# PortaCopos.net
KiCad netlist of a schematic drawn in EAGLE
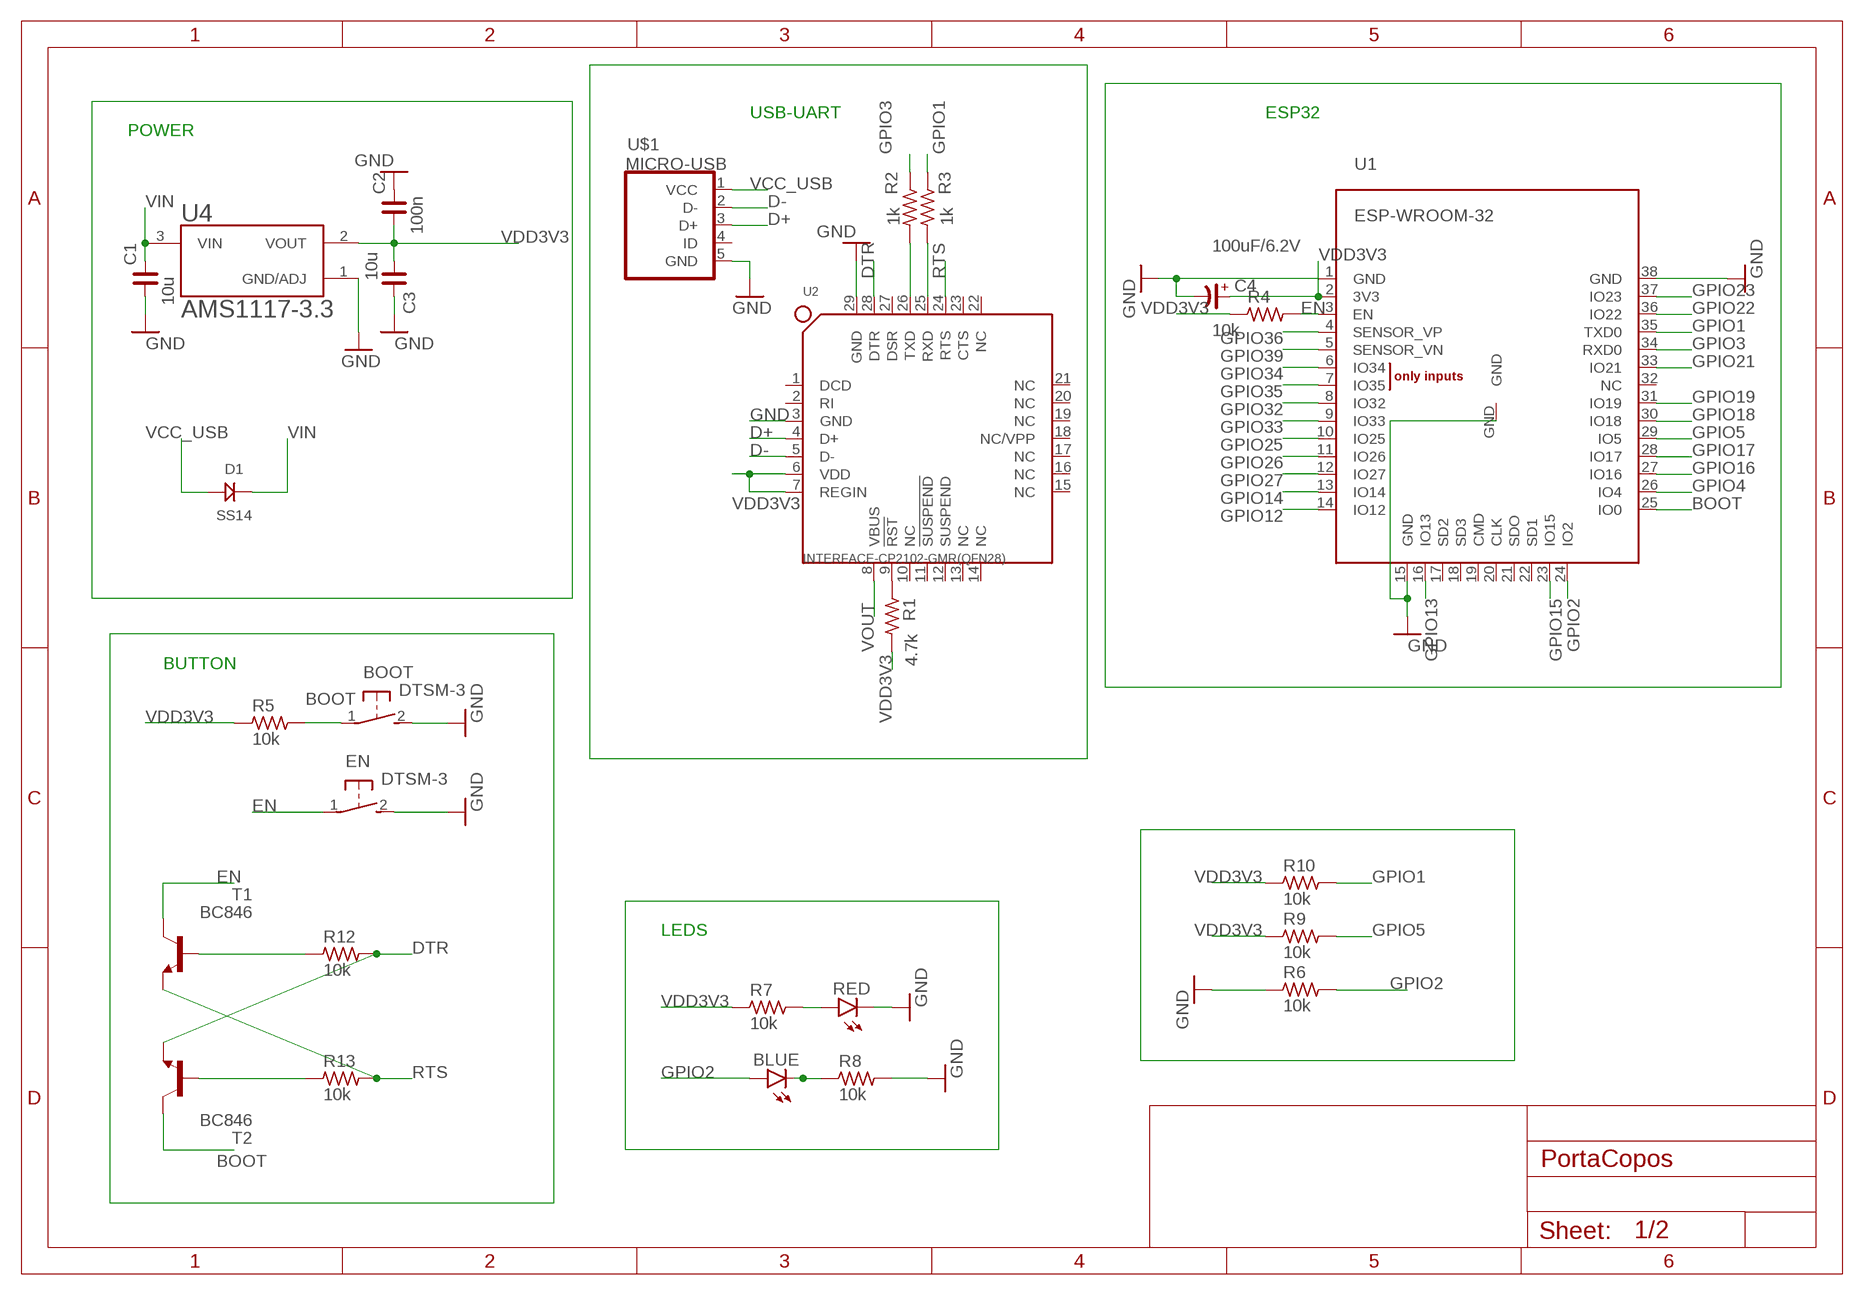
[diagram p0: schematic, sheet 1]
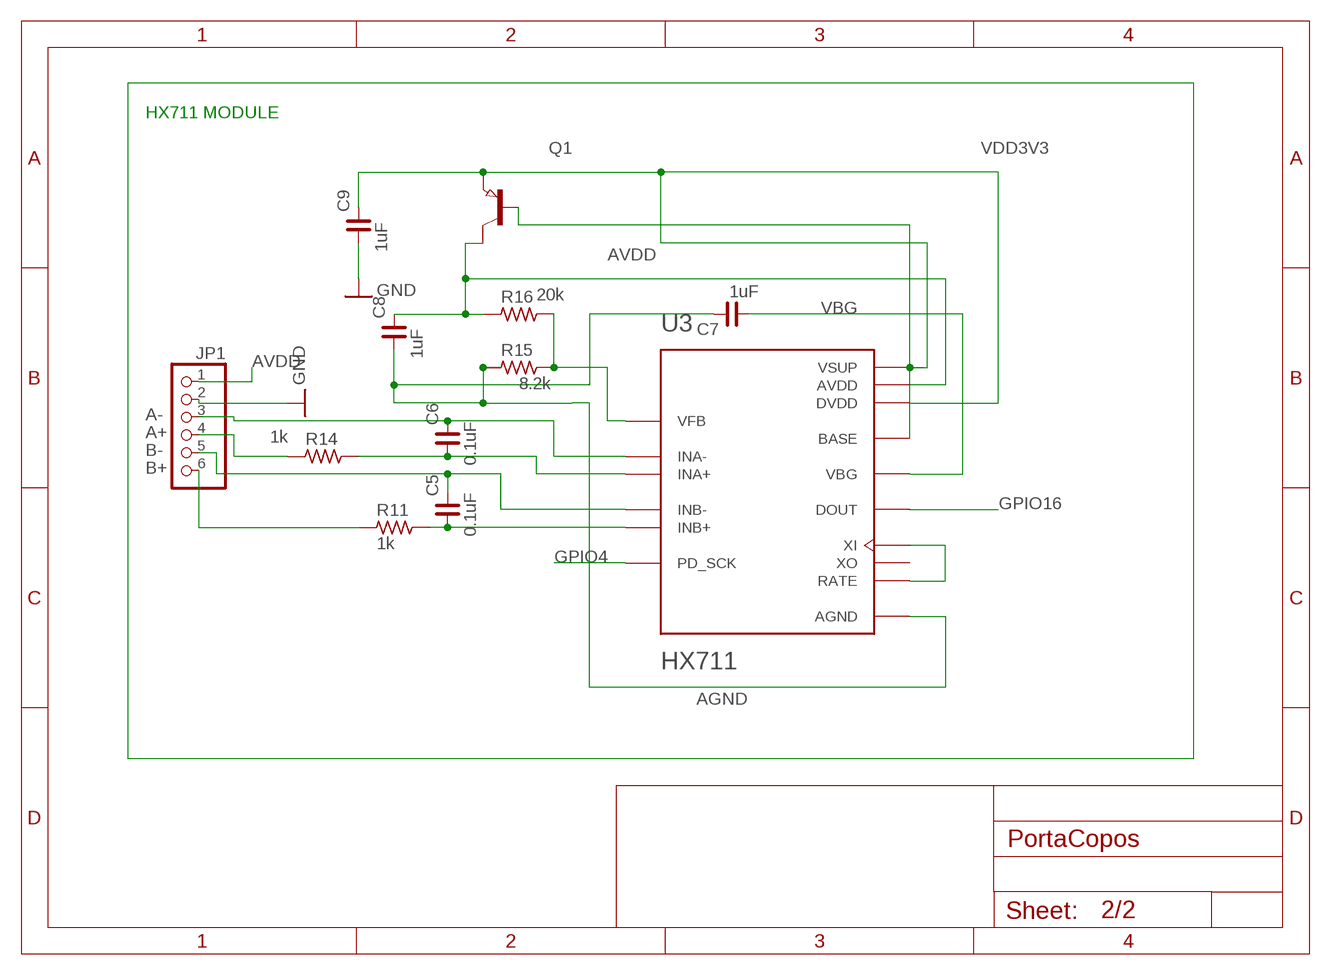
[diagram p1: schematic, sheet 2]

(export (version "E")
  (design (tool "Eeschema 10.0.6"))
  (components
    (comp (ref "BLUE")
      (value "blue")
      (footprint "eagle-import:CHIPLED_0603")
      (libsource (lib "eagle-import") (part "LEDCHIPLED_0603"))
    )
    (comp (ref "BOOT")
      (value "DTSM-3")
      (footprint "eagle-import:DTSM-3")
      (libsource (lib "eagle-import") (part "DTSM-3"))
    )
    (comp (ref "C1")
      (value "10u")
      (footprint "eagle-import:C0603")
      (libsource (lib "eagle-import") (part "C_0603"))
    )
    (comp (ref "C2")
      (value "100n")
      (footprint "eagle-import:C0603")
      (libsource (lib "eagle-import") (part "C_0603"))
    )
    (comp (ref "C3")
      (value "10u")
      (footprint "eagle-import:C0603")
      (libsource (lib "eagle-import") (part "C_0603"))
    )
    (comp (ref "C4")
      (value "100uF/6.2V")
      (footprint "eagle-import:C3216-18_T")
      (libsource (lib "eagle-import") (part "CP_3216-18"))
    )
    (comp (ref "D1")
      (value "SS14")
      (footprint "eagle-import:DO214")
      (fields (field (name "MF") "ON Semiconductor"))
      (libsource (lib "eagle-import") (part "SS14"))
    )
    (comp (ref "EN")
      (value "DTSM-3")
      (footprint "eagle-import:DTSM-3")
      (libsource (lib "eagle-import") (part "DTSM-3"))
    )
    (comp (ref "R1")
      (value "4.7k")
      (footprint "eagle-import:R0603")
      (libsource (lib "eagle-import") (part "R_0603"))
    )
    (comp (ref "R2")
      (value "1k")
      (footprint "eagle-import:R0603")
      (libsource (lib "eagle-import") (part "R_0603"))
    )
    (comp (ref "R3")
      (value "1k")
      (footprint "eagle-import:R0603")
      (libsource (lib "eagle-import") (part "R_0603"))
    )
    (comp (ref "R4")
      (value "10k")
      (footprint "eagle-import:R0603")
      (libsource (lib "eagle-import") (part "R_0603"))
    )
    (comp (ref "R5")
      (value "10k")
      (footprint "eagle-import:R0603")
      (libsource (lib "eagle-import") (part "R_0603"))
    )
    (comp (ref "R6")
      (value "10k")
      (footprint "eagle-import:R0603")
      (libsource (lib "eagle-import") (part "R_0603"))
    )
    (comp (ref "R7")
      (value "10k")
      (footprint "eagle-import:R0603")
      (libsource (lib "eagle-import") (part "R_0603"))
    )
    (comp (ref "R8")
      (value "10k")
      (footprint "eagle-import:R0603")
      (libsource (lib "eagle-import") (part "R_0603"))
    )
    (comp (ref "R9")
      (value "10k")
      (footprint "eagle-import:R0603")
      (libsource (lib "eagle-import") (part "R_0603"))
    )
    (comp (ref "R10")
      (value "10k")
      (footprint "eagle-import:R0603")
      (libsource (lib "eagle-import") (part "R_0603"))
    )
    (comp (ref "R12")
      (value "10k")
      (footprint "eagle-import:R0603")
      (libsource (lib "eagle-import") (part "R_0603"))
    )
    (comp (ref "R13")
      (value "10k")
      (footprint "eagle-import:R0603")
      (libsource (lib "eagle-import") (part "R_0603"))
    )
    (comp (ref "RED")
      (value "red")
      (footprint "eagle-import:CHIPLED_0603")
      (libsource (lib "eagle-import") (part "LEDCHIPLED_0603"))
    )
    (comp (ref "T1")
      (value "BC846")
      (footprint "eagle-import:SOT23")
      (libsource (lib "eagle-import") (part "BC846"))
    )
    (comp (ref "T2")
      (value "BC846")
      (footprint "eagle-import:SOT23")
      (libsource (lib "eagle-import") (part "BC846"))
    )
    (comp (ref "U$1")
      (value "MICRO-USB")
      (footprint "eagle-import:MICRO-USB-2")
      (libsource (lib "eagle-import") (part "MICRO-USB"))
    )
    (comp (ref "U1")
      (value "ESP-WROOM-32")
      (footprint "eagle-import:ESP-WROOM-32")
      (libsource (lib "eagle-import") (part "ESP-WROOM-32"))
    )
    (comp (ref "U2")
      (value "INTERFACE-CP2102-GMR(QFN28)")
      (footprint "eagle-import:QFN28G_0.5-5X5MM")
      (fields (field (name "MF") "Silicon") (field (name "MP") "CP2102-GMR"))
      (libsource (lib "eagle-import") (part "INTERFACE-CP2102-GMR(QFN28)"))
    )
    (comp (ref "U4")
      (value "AMS1117-3.3")
      (footprint "eagle-import:SOT229P700X180-4N")
      (fields (field (name "MF") "Advanced Monolithic Systems"))
      (libsource (lib "eagle-import") (part "AMS1117-3.3"))
    )
    (comp (ref "C5")
      (value "0.1uF")
      (footprint "eagle-import:C0805")
      (libsource (lib "eagle-import") (part "C_0805"))
    )
    (comp (ref "C6")
      (value "0.1uF")
      (footprint "eagle-import:C0805")
      (libsource (lib "eagle-import") (part "C_0805"))
    )
    (comp (ref "C7")
      (value "1uF")
      (footprint "eagle-import:C0805")
      (libsource (lib "eagle-import") (part "C_0805"))
    )
    (comp (ref "C8")
      (value "1uF")
      (footprint "eagle-import:C0805")
      (libsource (lib "eagle-import") (part "C_0805"))
    )
    (comp (ref "C9")
      (value "1uF")
      (footprint "eagle-import:C0805")
      (libsource (lib "eagle-import") (part "C_0805"))
    )
    (comp (ref "JP1")
      (value "PINHD-1X6")
      (footprint "eagle-import:1X06")
      (libsource (lib "eagle-import") (part "PINHD-1X6"))
    )
    (comp (ref "Q1")
      (value "PNP-TRANSISTOR_SOT23")
      (footprint "eagle-import:SOT23")
      (libsource (lib "eagle-import") (part "PNP-TRANSISTOR_SOT23"))
    )
    (comp (ref "R11")
      (value "1k")
      (footprint "eagle-import:R0603")
      (libsource (lib "eagle-import") (part "R_0603"))
    )
    (comp (ref "R14")
      (value "1k")
      (footprint "eagle-import:R0603")
      (libsource (lib "eagle-import") (part "R_0603"))
    )
    (comp (ref "R15")
      (value "8.2k")
      (footprint "eagle-import:R0603")
      (libsource (lib "eagle-import") (part "R_0603"))
    )
    (comp (ref "R16")
      (value "20k")
      (footprint "eagle-import:R0603")
      (libsource (lib "eagle-import") (part "R_0603"))
    )
    (comp (ref "U3")
      (value "HX711")
      (footprint "eagle-import:SOP127P600X180-16N")
      (fields (field (name "MF") "AVIA SEMICONDUCTOR"))
      (libsource (lib "eagle-import") (part "HX711"))
    )
  )
  (nets
    (net (code "1") (name "A+") (class "Default")
      (node (ref "JP1") (pin "4") (pinfunction "4_4") (pintype "passive"))
      (node (ref "R14") (pin "1") (pinfunction "1_1") (pintype "passive"))
    )
    (net (code "2") (name "A-") (class "Default")
      (node (ref "C6") (pin "2") (pinfunction "2_2") (pintype "passive"))
      (node (ref "JP1") (pin "3") (pinfunction "3_3") (pintype "passive"))
      (node (ref "U3") (pin "7") (pinfunction "INA-_7") (pintype "input"))
    )
    (net (code "3") (name "AGND") (class "Default")
      (node (ref "C7") (pin "2") (pinfunction "2_2") (pintype "passive"))
      (node (ref "C8") (pin "1") (pinfunction "1_1") (pintype "passive"))
      (node (ref "R15") (pin "1") (pinfunction "1_1") (pintype "passive"))
      (node (ref "U3") (pin "5") (pinfunction "AGND_5") (pintype "power_in"))
    )
    (net (code "4") (name "AVDD") (class "Default")
      (node (ref "C8") (pin "2") (pinfunction "2_2") (pintype "passive"))
      (node (ref "JP1") (pin "1") (pinfunction "1_1") (pintype "passive"))
      (node (ref "Q1") (pin "3") (pinfunction "C_3") (pintype "passive"))
      (node (ref "R16") (pin "1") (pinfunction "1_1") (pintype "passive"))
      (node (ref "U3") (pin "3") (pinfunction "AVDD_3") (pintype "power_in"))
    )
    (net (code "5") (name "B+") (class "Default")
      (node (ref "JP1") (pin "6") (pinfunction "6_6") (pintype "passive"))
      (node (ref "R11") (pin "1") (pinfunction "1_1") (pintype "passive"))
    )
    (net (code "6") (name "B-") (class "Default")
      (node (ref "C5") (pin "2") (pinfunction "2_2") (pintype "passive"))
      (node (ref "JP1") (pin "5") (pinfunction "5_5") (pintype "passive"))
      (node (ref "U3") (pin "9") (pinfunction "INB-_9") (pintype "input"))
    )
    (net (code "7") (name "BOOT") (class "Default")
      (node (ref "BOOT") (pin "1") (pinfunction "1_1") (pintype "passive"))
      (node (ref "R5") (pin "2") (pinfunction "2_2") (pintype "passive"))
      (node (ref "T2") (pin "3") (pinfunction "C_3") (pintype "passive"))
      (node (ref "U1") (pin "25") (pinfunction "IO0_25") (pintype "bidirectional"))
    )
    (net (code "8") (name "D+") (class "Default")
      (node (ref "U$1") (pin "3") (pinfunction "D+_3") (pintype "bidirectional"))
      (node (ref "U2") (pin "4") (pinfunction "D+_4") (pintype "bidirectional"))
    )
    (net (code "9") (name "D-") (class "Default")
      (node (ref "U$1") (pin "2") (pinfunction "D-_2") (pintype "bidirectional"))
      (node (ref "U2") (pin "5") (pinfunction "D-_5") (pintype "bidirectional"))
    )
    (net (code "10") (name "DTR") (class "Default")
      (node (ref "R12") (pin "2") (pinfunction "2_2") (pintype "passive"))
      (node (ref "T2") (pin "2") (pinfunction "E_2") (pintype "passive"))
      (node (ref "U2") (pin "28") (pinfunction "DTR_28") (pintype "bidirectional"))
    )
    (net (code "11") (name "EN") (class "Default")
      (node (ref "EN") (pin "1") (pinfunction "1_1") (pintype "passive"))
      (node (ref "R4") (pin "2") (pinfunction "2_2") (pintype "passive"))
      (node (ref "T1") (pin "3") (pinfunction "C_3") (pintype "passive"))
      (node (ref "U1") (pin "3") (pinfunction "EN_3") (pintype "bidirectional"))
    )
    (net (code "12") (name "GND") (class "Default")
      (node (ref "BOOT") (pin "2") (pinfunction "2_2") (pintype "passive"))
      (node (ref "C1") (pin "1") (pinfunction "1_1") (pintype "passive"))
      (node (ref "C2") (pin "2") (pinfunction "2_2") (pintype "passive"))
      (node (ref "C3") (pin "2") (pinfunction "2_2") (pintype "passive"))
      (node (ref "C4") (pin "-") (pinfunction "-_-") (pintype "passive"))
      (node (ref "C9") (pin "1") (pinfunction "1_1") (pintype "passive"))
      (node (ref "EN") (pin "2") (pinfunction "2_2") (pintype "passive"))
      (node (ref "JP1") (pin "2") (pinfunction "2_2") (pintype "passive"))
      (node (ref "R6") (pin "1") (pinfunction "1_1") (pintype "passive"))
      (node (ref "R8") (pin "2") (pinfunction "2_2") (pintype "passive"))
      (node (ref "RED") (pin "C") (pinfunction "C_C") (pintype "passive"))
      (node (ref "U$1") (pin "5") (pinfunction "GND_5") (pintype "power_in"))
      (node (ref "U1") (pin "1") (pinfunction "GND_1") (pintype "bidirectional"))
      (node (ref "U1") (pin "15") (pinfunction "GND_15") (pintype "bidirectional"))
      (node (ref "U1") (pin "38") (pinfunction "GND_38") (pintype "bidirectional"))
      (node (ref "U1") (pin "GND") (pinfunction "GND_GND") (pintype "bidirectional"))
      (node (ref "U2") (pin "29") (pinfunction "GND_29") (pintype "bidirectional"))
      (node (ref "U2") (pin "3") (pinfunction "GND_3") (pintype "bidirectional"))
      (node (ref "U4") (pin "1") (pinfunction "GND/ADJ_1") (pintype "power_in"))
    )
    (net (code "13") (name "GPIO1") (class "Default")
      (node (ref "R10") (pin "2") (pinfunction "2_2") (pintype "passive"))
      (node (ref "R3") (pin "1") (pinfunction "1_1") (pintype "passive"))
      (node (ref "U1") (pin "35") (pinfunction "TXD0_35") (pintype "bidirectional"))
    )
    (net (code "14") (name "GPIO2") (class "Default")
      (node (ref "BLUE") (pin "A") (pinfunction "A_A") (pintype "passive"))
      (node (ref "R6") (pin "2") (pinfunction "2_2") (pintype "passive"))
      (node (ref "U1") (pin "24") (pinfunction "IO2_24") (pintype "bidirectional"))
    )
    (net (code "15") (name "GPIO3") (class "Default")
      (node (ref "R2") (pin "1") (pinfunction "1_1") (pintype "passive"))
      (node (ref "U1") (pin "34") (pinfunction "RXD0_34") (pintype "bidirectional"))
    )
    (net (code "16") (name "GPIO4") (class "Default")
      (node (ref "U1") (pin "26") (pinfunction "IO4_26") (pintype "bidirectional"))
      (node (ref "U3") (pin "11") (pinfunction "PD_SCK_11") (pintype "input"))
    )
    (net (code "17") (name "GPIO5") (class "Default")
      (node (ref "R9") (pin "2") (pinfunction "2_2") (pintype "passive"))
      (node (ref "U1") (pin "29") (pinfunction "IO5_29") (pintype "bidirectional"))
    )
    (net (code "18") (name "GPIO12") (class "Default")
      (node (ref "U1") (pin "14") (pinfunction "IO12_14") (pintype "bidirectional"))
    )
    (net (code "19") (name "GPIO13") (class "Default")
      (node (ref "U1") (pin "16") (pinfunction "IO13_16") (pintype "bidirectional"))
    )
    (net (code "20") (name "GPIO14") (class "Default")
      (node (ref "U1") (pin "13") (pinfunction "IO14_13") (pintype "bidirectional"))
    )
    (net (code "21") (name "GPIO15") (class "Default")
      (node (ref "U1") (pin "23") (pinfunction "IO15_23") (pintype "bidirectional"))
    )
    (net (code "22") (name "GPIO16") (class "Default")
      (node (ref "U1") (pin "27") (pinfunction "IO16_27") (pintype "bidirectional"))
      (node (ref "U3") (pin "12") (pinfunction "DOUT_12") (pintype "output"))
    )
    (net (code "23") (name "GPIO17") (class "Default")
      (node (ref "U1") (pin "28") (pinfunction "IO17_28") (pintype "bidirectional"))
    )
    (net (code "24") (name "GPIO18") (class "Default")
      (node (ref "U1") (pin "30") (pinfunction "IO18_30") (pintype "bidirectional"))
    )
    (net (code "25") (name "GPIO19") (class "Default")
      (node (ref "U1") (pin "31") (pinfunction "IO19_31") (pintype "bidirectional"))
    )
    (net (code "26") (name "GPIO21") (class "Default")
      (node (ref "U1") (pin "33") (pinfunction "IO21_33") (pintype "bidirectional"))
    )
    (net (code "27") (name "GPIO22") (class "Default")
      (node (ref "U1") (pin "36") (pinfunction "IO22_36") (pintype "bidirectional"))
    )
    (net (code "28") (name "GPIO23") (class "Default")
      (node (ref "U1") (pin "37") (pinfunction "IO23_37") (pintype "bidirectional"))
    )
    (net (code "29") (name "GPIO25") (class "Default")
      (node (ref "U1") (pin "10") (pinfunction "IO25_10") (pintype "bidirectional"))
    )
    (net (code "30") (name "GPIO26") (class "Default")
      (node (ref "U1") (pin "11") (pinfunction "IO26_11") (pintype "bidirectional"))
    )
    (net (code "31") (name "GPIO27") (class "Default")
      (node (ref "U1") (pin "12") (pinfunction "IO27_12") (pintype "bidirectional"))
    )
    (net (code "32") (name "GPIO32") (class "Default")
      (node (ref "U1") (pin "8") (pinfunction "IO32_8") (pintype "bidirectional"))
    )
    (net (code "33") (name "GPIO33") (class "Default")
      (node (ref "U1") (pin "9") (pinfunction "IO33_9") (pintype "bidirectional"))
    )
    (net (code "34") (name "GPIO34") (class "Default")
      (node (ref "U1") (pin "6") (pinfunction "IO34_6") (pintype "input"))
    )
    (net (code "35") (name "GPIO35") (class "Default")
      (node (ref "U1") (pin "7") (pinfunction "IO35_7") (pintype "input"))
    )
    (net (code "36") (name "GPIO36") (class "Default")
      (node (ref "U1") (pin "4") (pinfunction "SENSOR_VP_4") (pintype "input"))
    )
    (net (code "37") (name "GPIO39") (class "Default")
      (node (ref "U1") (pin "5") (pinfunction "SENSOR_VN_5") (pintype "input"))
    )
    (net (code "38") (name "Net-(BLUE-PadC)") (class "Default")
      (node (ref "BLUE") (pin "C") (pinfunction "C_C") (pintype "passive"))
      (node (ref "R8") (pin "1") (pinfunction "1_1") (pintype "passive"))
    )
    (net (code "39") (name "Net-(R7-Pad2)") (class "Default")
      (node (ref "R7") (pin "2") (pinfunction "2_2") (pintype "passive"))
      (node (ref "RED") (pin "A") (pinfunction "A_A") (pintype "passive"))
    )
    (net (code "40") (name "Net-(T1-B)") (class "Default")
      (node (ref "R12") (pin "1") (pinfunction "1_1") (pintype "passive"))
      (node (ref "T1") (pin "1") (pinfunction "B_1") (pintype "passive"))
    )
    (net (code "41") (name "Net-(T2-B)") (class "Default")
      (node (ref "R13") (pin "1") (pinfunction "1_1") (pintype "passive"))
      (node (ref "T2") (pin "1") (pinfunction "B_1") (pintype "passive"))
    )
    (net (code "42") (name "Net-(U2-RXD)") (class "Default")
      (node (ref "R3") (pin "2") (pinfunction "2_2") (pintype "passive"))
      (node (ref "U2") (pin "25") (pinfunction "RXD_25") (pintype "bidirectional"))
    )
    (net (code "43") (name "Net-(U2-TXD)") (class "Default")
      (node (ref "R2") (pin "2") (pinfunction "2_2") (pintype "passive"))
      (node (ref "U2") (pin "26") (pinfunction "TXD_26") (pintype "bidirectional"))
    )
    (net (code "44") (name "Net-(U2-~{RST})") (class "Default")
      (node (ref "R1") (pin "1") (pinfunction "1_1") (pintype "passive"))
      (node (ref "U2") (pin "9") (pinfunction "~{RST}_9") (pintype "bidirectional"))
    )
    (net (code "45") (name "Net-(U3-INA+)") (class "Default")
      (node (ref "C6") (pin "1") (pinfunction "1_1") (pintype "passive"))
      (node (ref "R14") (pin "2") (pinfunction "2_2") (pintype "passive"))
      (node (ref "U3") (pin "8") (pinfunction "INA+_8") (pintype "input"))
    )
    (net (code "46") (name "Net-(U3-INB+)") (class "Default")
      (node (ref "C5") (pin "1") (pinfunction "1_1") (pintype "passive"))
      (node (ref "R11") (pin "2") (pinfunction "2_2") (pintype "passive"))
      (node (ref "U3") (pin "10") (pinfunction "INB+_10") (pintype "input"))
    )
    (net (code "47") (name "Net-(U3-RATE)") (class "Default")
      (node (ref "U3") (pin "14") (pinfunction "XI_14") (pintype "input"))
      (node (ref "U3") (pin "15") (pinfunction "RATE_15") (pintype "input"))
    )
    (net (code "48") (name "Net-(U3-VFB)") (class "Default")
      (node (ref "R15") (pin "2") (pinfunction "2_2") (pintype "passive"))
      (node (ref "R16") (pin "2") (pinfunction "2_2") (pintype "passive"))
      (node (ref "U3") (pin "4") (pinfunction "VFB_4") (pintype "input"))
    )
    (net (code "49") (name "RTS") (class "Default")
      (node (ref "R13") (pin "2") (pinfunction "2_2") (pintype "passive"))
      (node (ref "T1") (pin "2") (pinfunction "E_2") (pintype "passive"))
      (node (ref "U2") (pin "24") (pinfunction "RTS_24") (pintype "bidirectional"))
    )
    (net (code "50") (name "VBG") (class "Default")
      (node (ref "C7") (pin "1") (pinfunction "1_1") (pintype "passive"))
      (node (ref "U3") (pin "6") (pinfunction "VBG_6") (pintype "output"))
    )
    (net (code "51") (name "VCC_USB") (class "Default")
      (node (ref "D1") (pin "ANODE") (pinfunction "ANODE_ANODE") (pintype "bidirectional"))
      (node (ref "U$1") (pin "1") (pinfunction "VCC_1") (pintype "power_in"))
    )
    (net (code "52") (name "VDD3V3") (class "Default")
      (node (ref "C2") (pin "1") (pinfunction "1_1") (pintype "passive"))
      (node (ref "C3") (pin "1") (pinfunction "1_1") (pintype "passive"))
      (node (ref "C4") (pin "+") (pinfunction "+_+") (pintype "passive"))
      (node (ref "C9") (pin "2") (pinfunction "2_2") (pintype "passive"))
      (node (ref "Q1") (pin "1") (pinfunction "B_1") (pintype "passive"))
      (node (ref "Q1") (pin "2") (pinfunction "E_2") (pintype "passive"))
      (node (ref "R1") (pin "2") (pinfunction "2_2") (pintype "passive"))
      (node (ref "R10") (pin "1") (pinfunction "1_1") (pintype "passive"))
      (node (ref "R4") (pin "1") (pinfunction "1_1") (pintype "passive"))
      (node (ref "R5") (pin "1") (pinfunction "1_1") (pintype "passive"))
      (node (ref "R7") (pin "1") (pinfunction "1_1") (pintype "passive"))
      (node (ref "R9") (pin "1") (pinfunction "1_1") (pintype "passive"))
      (node (ref "U1") (pin "2") (pinfunction "3V3_2") (pintype "bidirectional"))
      (node (ref "U2") (pin "6") (pinfunction "VDD_6") (pintype "bidirectional"))
      (node (ref "U2") (pin "7") (pinfunction "REGIN_7") (pintype "bidirectional"))
      (node (ref "U3") (pin "1") (pinfunction "VSUP_1") (pintype "power_in"))
      (node (ref "U3") (pin "16") (pinfunction "DVDD_16") (pintype "power_in"))
      (node (ref "U3") (pin "2") (pinfunction "BASE_2") (pintype "output"))
      (node (ref "U4") (pin "2") (pinfunction "VOUT_2") (pintype "output"))
    )
    (net (code "53") (name "VIN") (class "Default")
      (node (ref "C1") (pin "2") (pinfunction "2_2") (pintype "passive"))
      (node (ref "D1") (pin "CATHODE") (pinfunction "KATHODE_CATHODE") (pintype "bidirectional"))
      (node (ref "U4") (pin "3") (pinfunction "VIN_3") (pintype "input"))
    )
    (net (code "54") (name "VOUT") (class "Default")
      (node (ref "U2") (pin "8") (pinfunction "VBUS_8") (pintype "bidirectional"))
    )
    (net (code "55") (name "unconnected-(U$1-ID-Pad4)") (class "Default")
      (node (ref "U$1") (pin "4") (pinfunction "ID_4") (pintype "bidirectional"))
    )
    (net (code "56") (name "unconnected-(U1-CLK-Pad20)") (class "Default")
      (node (ref "U1") (pin "20") (pinfunction "CLK_20") (pintype "bidirectional"))
    )
    (net (code "57") (name "unconnected-(U1-CMD-Pad19)") (class "Default")
      (node (ref "U1") (pin "19") (pinfunction "CMD_19") (pintype "bidirectional"))
    )
    (net (code "58") (name "unconnected-(U1-NC-Pad32)") (class "Default")
      (node (ref "U1") (pin "32") (pinfunction "NC_32") (pintype "bidirectional"))
    )
    (net (code "59") (name "unconnected-(U1-SD1-Pad22)") (class "Default")
      (node (ref "U1") (pin "22") (pinfunction "SD1_22") (pintype "bidirectional"))
    )
    (net (code "60") (name "unconnected-(U1-SD2-Pad17)") (class "Default")
      (node (ref "U1") (pin "17") (pinfunction "SD2_17") (pintype "bidirectional"))
    )
    (net (code "61") (name "unconnected-(U1-SD3-Pad18)") (class "Default")
      (node (ref "U1") (pin "18") (pinfunction "SD3_18") (pintype "bidirectional"))
    )
    (net (code "62") (name "unconnected-(U1-SDO-Pad21)") (class "Default")
      (node (ref "U1") (pin "21") (pinfunction "SDO_21") (pintype "bidirectional"))
    )
    (net (code "63") (name "unconnected-(U2-CTS-Pad23)") (class "Default")
      (node (ref "U2") (pin "23") (pinfunction "CTS_23") (pintype "bidirectional"))
    )
    (net (code "64") (name "unconnected-(U2-DCD-Pad1)") (class "Default")
      (node (ref "U2") (pin "1") (pinfunction "DCD_1") (pintype "bidirectional"))
    )
    (net (code "65") (name "unconnected-(U2-DSR-Pad27)") (class "Default")
      (node (ref "U2") (pin "27") (pinfunction "DSR_27") (pintype "bidirectional"))
    )
    (net (code "66") (name "unconnected-(U2-NC-Pad10)") (class "Default")
      (node (ref "U2") (pin "10") (pinfunction "NC_10") (pintype "bidirectional"))
    )
    (net (code "67") (name "unconnected-(U2-NC-Pad13)") (class "Default")
      (node (ref "U2") (pin "13") (pinfunction "NC_13") (pintype "bidirectional"))
    )
    (net (code "68") (name "unconnected-(U2-NC-Pad14)") (class "Default")
      (node (ref "U2") (pin "14") (pinfunction "NC_14") (pintype "bidirectional"))
    )
    (net (code "69") (name "unconnected-(U2-NC-Pad15)") (class "Default")
      (node (ref "U2") (pin "15") (pinfunction "NC_15") (pintype "bidirectional"))
    )
    (net (code "70") (name "unconnected-(U2-NC-Pad16)") (class "Default")
      (node (ref "U2") (pin "16") (pinfunction "NC_16") (pintype "bidirectional"))
    )
    (net (code "71") (name "unconnected-(U2-NC-Pad17)") (class "Default")
      (node (ref "U2") (pin "17") (pinfunction "NC_17") (pintype "bidirectional"))
    )
    (net (code "72") (name "unconnected-(U2-NC-Pad19)") (class "Default")
      (node (ref "U2") (pin "19") (pinfunction "NC_19") (pintype "bidirectional"))
    )
    (net (code "73") (name "unconnected-(U2-NC-Pad20)") (class "Default")
      (node (ref "U2") (pin "20") (pinfunction "NC_20") (pintype "bidirectional"))
    )
    (net (code "74") (name "unconnected-(U2-NC-Pad21)") (class "Default")
      (node (ref "U2") (pin "21") (pinfunction "NC_21") (pintype "bidirectional"))
    )
    (net (code "75") (name "unconnected-(U2-NC-Pad22)") (class "Default")
      (node (ref "U2") (pin "22") (pinfunction "NC_22") (pintype "bidirectional"))
    )
    (net (code "76") (name "unconnected-(U2-NC{slash}VPP-Pad18)") (class "Default")
      (node (ref "U2") (pin "18") (pinfunction "NC/VPP_18") (pintype "bidirectional"))
    )
    (net (code "77") (name "unconnected-(U2-RI-Pad2)") (class "Default")
      (node (ref "U2") (pin "2") (pinfunction "RI_2") (pintype "bidirectional"))
    )
    (net (code "78") (name "unconnected-(U2-SUSPEND-Pad12)") (class "Default")
      (node (ref "U2") (pin "12") (pinfunction "SUSPEND_12") (pintype "bidirectional"))
    )
    (net (code "79") (name "unconnected-(U2-~{SUSPEND}-Pad11)") (class "Default")
      (node (ref "U2") (pin "11") (pinfunction "~{SUSPEND}_11") (pintype "bidirectional"))
    )
    (net (code "80") (name "unconnected-(U3-XO-Pad13)") (class "Default")
      (node (ref "U3") (pin "13") (pinfunction "XO_13") (pintype "output"))
    )
  )
)
